# connectors.net
KiCad netlist of a schematic drawn in Altium Designer
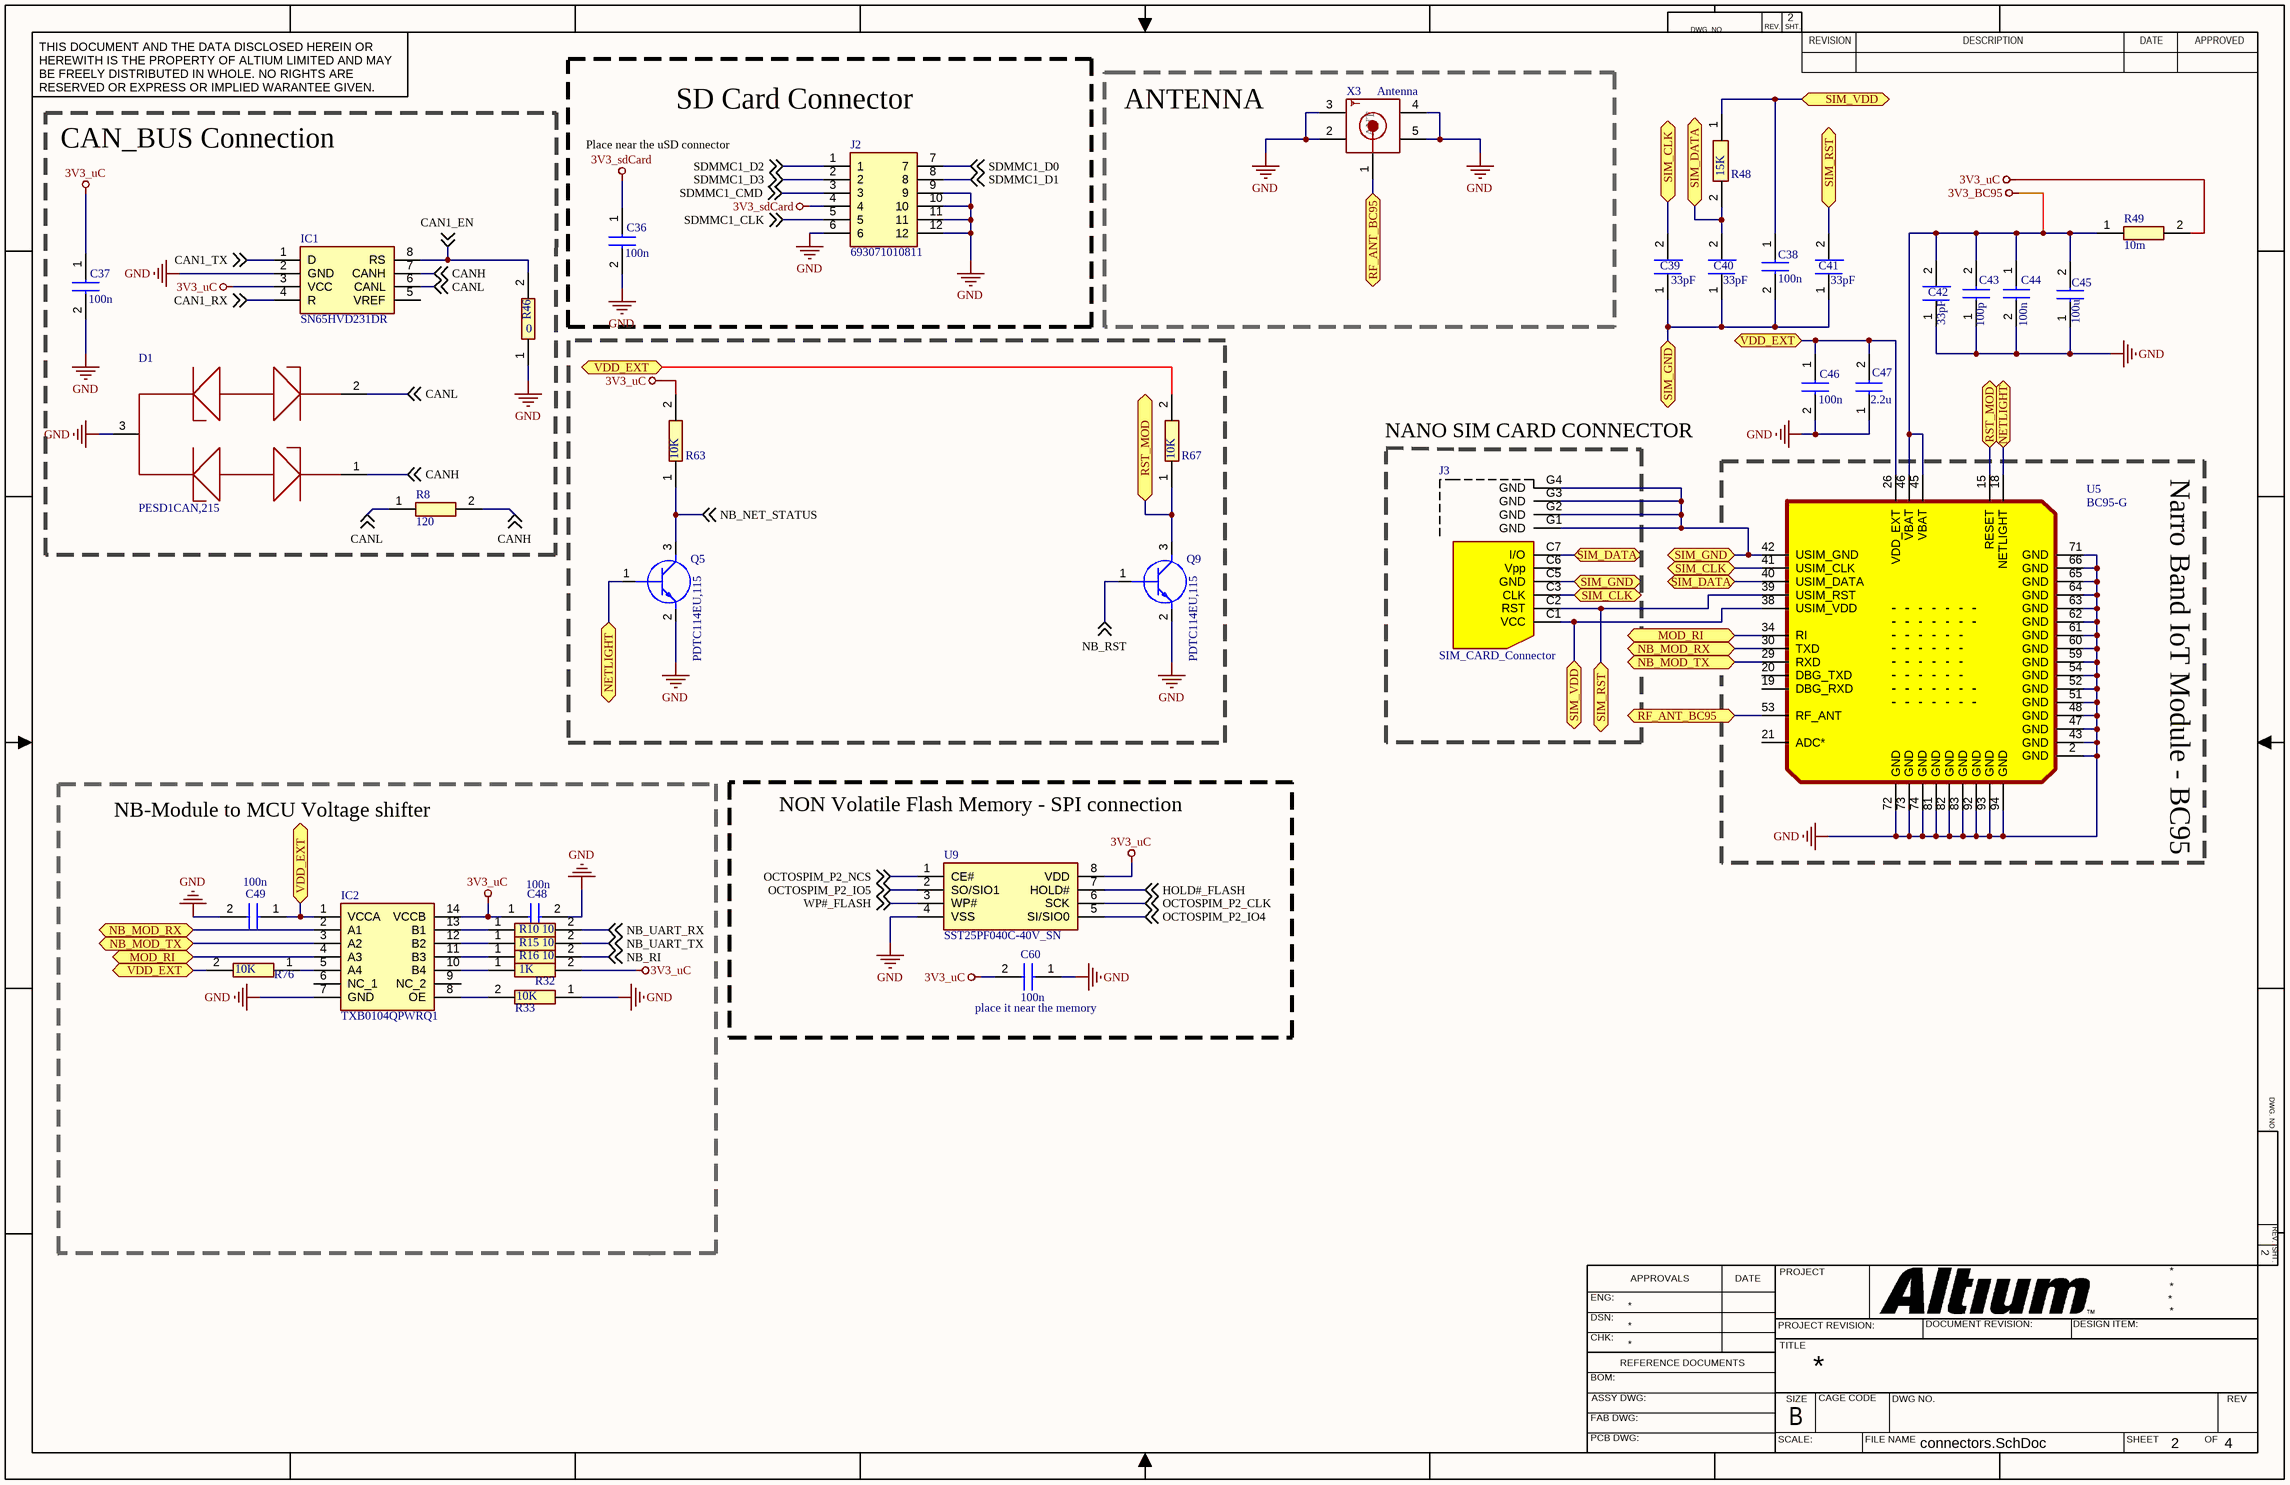
[diagram p0: connectors.SchDoc]

(export (version "E")
  (design (tool "Eeschema 10.0.6"))
  (components
    (comp (ref "C36")
      (value "100n")
      (footprint "SamacSys:CAPC1608X87N")
      (description "Capacitor")
      (fields (field (name "MANUFACTURER_PART_NUMBER") "885012206071"))
      (libsource (lib "*") (part "885012206071"))
    )
    (comp (ref "C37")
      (value "100n")
      (footprint "SamacSys:CAPC1608X87N")
      (description "Capacitor")
      (fields (field (name "MANUFACTURER_PART_NUMBER") "885012206071"))
      (libsource (lib "*") (part "885012206071"))
    )
    (comp (ref "C38")
      (value "100n")
      (footprint "SamacSys:CAPC1608X87N")
      (description "Capacitor")
      (fields (field (name "MANUFACTURER_PART_NUMBER") "885012206071"))
      (libsource (lib "*") (part "885012206071"))
    )
    (comp (ref "C39")
      (value "33pF")
      (footprint "CAPC1608X87N")
      (description "Cap Ceramic 33pF 25V C0G 10% SMD 0603 125°C Paper T/R")
      (fields
        (field (name "MANUFACTURER") "Vishay Vitramon")
        (field (name "MANUFACTURER PART NUMBER") "VJ0603A330KXXCW1BC")
      )
      (libsource (lib "shm_schem_lib") (part "VJ0603A330KXXCW1BC"))
    )
    (comp (ref "C40")
      (value "33pF")
      (footprint "CAPC1608X87N")
      (description "Cap Ceramic 33pF 25V C0G 10% SMD 0603 125°C Paper T/R")
      (fields
        (field (name "MANUFACTURER") "Vishay Vitramon")
        (field (name "MANUFACTURER PART NUMBER") "VJ0603A330KXXCW1BC")
      )
      (libsource (lib "shm_schem_lib") (part "VJ0603A330KXXCW1BC"))
    )
    (comp (ref "C41")
      (value "33pF")
      (footprint "CAPC1608X87N")
      (description "Cap Ceramic 33pF 25V C0G 10% SMD 0603 125°C Paper T/R")
      (fields
        (field (name "MANUFACTURER") "Vishay Vitramon")
        (field (name "MANUFACTURER PART NUMBER") "VJ0603A330KXXCW1BC")
      )
      (libsource (lib "shm_schem_lib") (part "VJ0603A330KXXCW1BC"))
    )
    (comp (ref "C42")
      (value "33pF")
      (footprint "CAPC1608X87N")
      (description "Cap Ceramic 33pF 25V C0G 10% SMD 0603 125°C Paper T/R")
      (fields
        (field (name "MANUFACTURER") "Vishay Vitramon")
        (field (name "MANUFACTURER PART NUMBER") "VJ0603A330KXXCW1BC")
      )
      (libsource (lib "shm_schem_lib") (part "VJ0603A330KXXCW1BC"))
    )
    (comp (ref "C43")
      (value "100p")
      (footprint "SamacSys:CAPC1608X87N")
      (description "Capacitor")
      (fields (field (name "MANUFACTURER_PART_NUMBER") "885012206003"))
      (libsource (lib "*") (part "885012206003"))
    )
    (comp (ref "C44")
      (value "100n")
      (footprint "SamacSys:CAPC1608X87N")
      (description "Capacitor")
      (fields (field (name "MANUFACTURER_PART_NUMBER") "885012206071"))
      (libsource (lib "*") (part "885012206071"))
    )
    (comp (ref "C45")
      (value "100u")
      (footprint "SamacSys:CAPC3216X180N")
      (description "Capacitor")
      (fields
        (field (name "MOUSER2 PART NUMBER") "81-GRM31CR60J107ME9L")
        (field (name "MANUFACTURER_PART_NUMBER") "GRM31CR60J107ME39L")
      )
      (libsource (lib "*") (part "GRM31CR60J107ME39L"))
    )
    (comp (ref "C46")
      (value "100n")
      (footprint "SamacSys:CAPC1608X87N")
      (description "Capacitor")
      (fields (field (name "MANUFACTURER_PART_NUMBER") "885012206071"))
      (libsource (lib "*") (part "885012206071"))
    )
    (comp (ref "C47")
      (value "2.2u")
      (footprint "SamacSys:CAPC1608X50N")
      (description "Capacitor")
      (fields (field (name "MANUFACTURER_PART_NUMBER") "EMK107BJ225KA-T"))
      (libsource (lib "*") (part "EMK107BJ225KA-T"))
    )
    (comp (ref "C48")
      (value "100n")
      (footprint "SamacSys:CAPC1608X87N")
      (description "Capacitor")
      (fields (field (name "MANUFACTURER_PART_NUMBER") "885012206071"))
      (libsource (lib "*") (part "885012206071"))
    )
    (comp (ref "C49")
      (value "100n")
      (footprint "SamacSys:CAPC1608X87N")
      (description "Capacitor")
      (fields (field (name "MANUFACTURER_PART_NUMBER") "885012206071"))
      (libsource (lib "*") (part "885012206071"))
    )
    (comp (ref "C60")
      (value "100n")
      (footprint "SamacSys:CAPC1608X87N")
      (description "Capacitor")
      (fields (field (name "MANUFACTURER_PART_NUMBER") "885012206071"))
      (libsource (lib "*") (part "885012206071"))
    )
    (comp (ref "D1")
      (value "PESD1CAN,215")
      (footprint "SOT95P230X110-3N")
      (description "ESD Suppressor Diode TVS Bi-Dir 24V Automotive 3-Pin SOT-23 T/R / TVS DIODE 24VWM 70VC SOT23")
      (fields (field (name "MANUFACTURER") "Nexperia"))
      (libsource (lib "shm_schem_lib") (part "PESD1CAN,215"))
    )
    (comp (ref "IC1")
      (value "SN65HVD231DR")
      (footprint "SamacSys:SOIC127P600X175-8N")
      (description "Integrated Circuit")
      (libsource (lib "*") (part "SN65HVD231DR"))
    )
    (comp (ref "IC2")
      (value "TXB0104QPWRQ1")
      (footprint "SOP65P640X120-14N")
      (description "Integrated Circuit")
      (fields (field (name "MOUSER2 PART NUMBER") "595-TXB0104QPWRQ1"))
      (libsource (lib "*") (part "TXB0104QPWRQ1"))
    )
    (comp (ref "J2")
      (value "693071010811")
      (footprint "SamacSys:693071010811")
      (description "Connector")
      (libsource (lib "*") (part "693071010811"))
    )
    (comp (ref "J3")
      (value "SIM_CARD_Connector")
      (footprint "SIM8060601400A")
      (description "Sim Nano Hinged, 6P, 1.40MM Prof")
      (fields
        (field (name "MANUFACTURER") "GCT")
        (field (name "MANUFACTURER PART NUMBER") "SIM8060-6-0-14-00-A")
      )
      (libsource (lib "shm_schem_lib") (part "SIM8060-6-0-14-00-A"))
    )
    (comp (ref "Q5")
      (value "PDTC114EU,115")
      (footprint "SamacSys:SOT65P210X110-3N")
      (description "Transistor BJT NPN")
      (fields (field (name "MOUSER2 PART NUMBER") "771-PDTC114EU115"))
      (libsource (lib "*") (part "PDTC114EU,115"))
    )
    (comp (ref "Q9")
      (value "PDTC114EU,115")
      (footprint "SamacSys:SOT65P210X110-3N")
      (description "Transistor BJT NPN")
      (fields (field (name "MOUSER2 PART NUMBER") "771-PDTC114EU115"))
      (libsource (lib "*") (part "PDTC114EU,115"))
    )
    (comp (ref "R8")
      (value "120")
      (footprint "ERA2V_(0402)")
      (description "Resistor")
      (fields (field (name "MANUFACTURER_PART_NUMBER") "ERA-2VEB1200X"))
      (libsource (lib "*") (part "ERA-2VEB1200X"))
    )
    (comp (ref "R10")
      (value "10")
      (footprint "SamacSys:RESC1005X40N")
      (description "Resistor")
      (fields (field (name "MANUFACTURER_PART_NUMBER") "CR0402-FX-10R0GLF"))
      (libsource (lib "*") (part "CR0402-FX-10R0GLF"))
    )
    (comp (ref "R15")
      (value "10")
      (footprint "SamacSys:RESC1005X40N")
      (description "Resistor")
      (fields (field (name "MANUFACTURER_PART_NUMBER") "CR0402-FX-10R0GLF"))
      (libsource (lib "*") (part "CR0402-FX-10R0GLF"))
    )
    (comp (ref "R16")
      (value "10")
      (footprint "SamacSys:RESC1005X40N")
      (description "Resistor")
      (fields (field (name "MANUFACTURER_PART_NUMBER") "CR0402-FX-10R0GLF"))
      (libsource (lib "*") (part "CR0402-FX-10R0GLF"))
    )
    (comp (ref "R32")
      (value "1K")
      (footprint "RESC1608X55N")
      (description "Resistor")
      (fields
        (field (name "MOUSER2 PART NUMBER") "71-CRCW06031K00FKEAC")
        (field (name "MANUFACTURER_PART_NUMBER") "CRCW06031K00FKEAC")
      )
      (libsource (lib "*") (part "CRCW06031K00FKEAC"))
    )
    (comp (ref "R33")
      (value "10K")
      (footprint "ERJ3EK_(0603)")
      (description "Resistor")
      (fields
        (field (name "MOUSER2 PART NUMBER") "667-ERJ-3EKF1002V")
        (field (name "MANUFACTURER_PART_NUMBER") "ERJ-3EKF1002V")
      )
      (libsource (lib "*") (part "ERJ-3EKF1002V"))
    )
    (comp (ref "R46")
      (value "0")
      (footprint "SamacSys:RESC1608X55N")
      (description "Resistor")
      (fields (field (name "MANUFACTURER_PART_NUMBER") "RC0603FR-070RL"))
      (libsource (lib "*") (part "RC0603FR-070RL"))
    )
    (comp (ref "R48")
      (value "15K")
      (footprint "RESC1508X50N")
      (description "Res Thick Film 0603 15K Ohm 1% 0.25W(1/4W) ±100ppm/°C Pad SMD Automotive Medical T/R")
      (fields
        (field (name "MANUFACTURER") "Vishay Dale")
        (field (name "MANUFACTURER PART NUMBER") "RCS060315K0FKEA")
      )
      (libsource (lib "shm_schem_lib") (part "RCS060315K0FKEA"))
    )
    (comp (ref "R49")
      (value "10m")
      (footprint "ERJ6_B_BW_R_LW_CW_D")
      (description "Resistor")
      (fields
        (field (name "MOUSER2 PART NUMBER") "667-ERJ-6CWDR010V")
        (field (name "MANUFACTURER_PART_NUMBER") "ERJ-6CWDR010V")
      )
      (libsource (lib "*") (part "ERJ-6CWDR010V"))
    )
    (comp (ref "R63")
      (value "10K")
      (footprint "SamacSys:ERJ3EK_(0603)")
      (description "Resistor")
      (fields
        (field (name "MOUSER2 PART NUMBER") "667-ERJ-3EKF1002V")
        (field (name "MANUFACTURER_PART_NUMBER") "ERJ-3EKF1002V")
      )
      (libsource (lib "") (part "ERJ-3EKF1002V_1"))
    )
    (comp (ref "R67")
      (value "10K")
      (footprint "SamacSys:ERJ3EK_(0603)")
      (description "Resistor")
      (fields
        (field (name "MOUSER2 PART NUMBER") "667-ERJ-3EKF1002V")
        (field (name "MANUFACTURER_PART_NUMBER") "ERJ-3EKF1002V")
      )
      (libsource (lib "") (part "ERJ-3EKF1002V_1"))
    )
    (comp (ref "R76")
      (value "10K")
      (footprint "SamacSys:ERJ3EK_(0603)")
      (description "Resistor")
      (fields
        (field (name "MOUSER2 PART NUMBER") "667-ERJ-3EKF1002V")
        (field (name "MANUFACTURER_PART_NUMBER") "ERJ-3EKF1002V")
      )
      (libsource (lib "*") (part "ERJ-3EKF1002V"))
    )
    (comp (ref "U5")
      (value "BC95-G")
      (footprint "XCVR_BC95GJB02STD")
      (description "NB IoT Click BC95 LTE CAT NB1 Module Add-On Board")
      (fields
        (field (name "MANUFACTURER") "mikroElektronika")
        (field (name "MANUFACTURER PART NUMBER") "MIKROE-3294")
      )
      (libsource (lib "shm_schem_lib") (part "MIKROE-3294"))
    )
    (comp (ref "U9")
      (value "SST25PF040C-40V_SN")
      (footprint "SamacSys:SOIC127P600X175-8N")
      (description "Integrated Circuit")
      (fields (field (name "MANUFACTURER_PART_NUMBER") "SST25PF040C-40V/SN"))
      (libsource (lib "*") (part "SST25PF040C-40V_SN"))
    )
    (comp (ref "X3")
      (value "Antenna")
      (footprint "PCBSMAFRAHT")
      (description "CONNSMAJACKR/A50OHMPCB")
      (fields
        (field (name "MANUFACTURER") "Taoglas")
        (field (name "MANUFACTURER PART NUMBER") "PCB.SMAFRA.HT")
      )
      (libsource (lib "shm_schem_lib") (part "PCB.SMAFRA.HT"))
    )
  )
  (nets
    (net (code "1") (name "/MOD_RI") (class "Default")
      (node (ref "IC2") (pin "4") (pinfunction "A3_4") (pintype "passive"))
      (node (ref "U5") (pin "34") (pinfunction "RI_34") (pintype "passive"))
    )
    (net (code "2") (name "/NB_MOD_RX") (class "Default")
      (node (ref "IC2") (pin "2") (pinfunction "A1_2") (pintype "passive"))
      (node (ref "U5") (pin "30") (pinfunction "TXD_30") (pintype "passive"))
    )
    (net (code "3") (name "/NB_MOD_TX") (class "Default")
      (node (ref "IC2") (pin "3") (pinfunction "A2_3") (pintype "passive"))
      (node (ref "U5") (pin "29") (pinfunction "RXD_29") (pintype "passive"))
    )
    (net (code "4") (name "/NETLIGHT") (class "Default")
      (node (ref "Q5") (pin "1") (pinfunction "B_1") (pintype "passive"))
      (node (ref "U5") (pin "18") (pinfunction "NETLIGHT_18") (pintype "passive"))
    )
    (net (code "5") (name "/RF_ANT_BC95") (class "Default")
      (node (ref "U5") (pin "53") (pinfunction "RF_ANT_53") (pintype "passive"))
      (node (ref "X3") (pin "1") (pinfunction "1_1") (pintype "passive"))
    )
    (net (code "6") (name "/RST_MOD") (class "Default")
      (node (ref "Q9") (pin "3") (pinfunction "C_3") (pintype "passive"))
      (node (ref "R67") (pin "1") (pinfunction "1_1") (pintype "passive"))
      (node (ref "U5") (pin "15") (pinfunction "RESET_15") (pintype "passive"))
    )
    (net (code "7") (name "/SIM_CLK") (class "Default")
      (node (ref "C39") (pin "2") (pinfunction "2_2") (pintype "passive"))
      (node (ref "J3") (pin "C3") (pinfunction "CLK_C3") (pintype "passive"))
      (node (ref "U5") (pin "41") (pinfunction "USIM_CLK_41") (pintype "passive"))
    )
    (net (code "8") (name "/SIM_DATA") (class "Default")
      (node (ref "C40") (pin "2") (pinfunction "2_2") (pintype "passive"))
      (node (ref "J3") (pin "C7") (pinfunction "I/O_C7") (pintype "passive"))
      (node (ref "R48") (pin "2") (pinfunction "2_2") (pintype "passive"))
      (node (ref "U5") (pin "40") (pinfunction "USIM_DATA_40") (pintype "passive"))
    )
    (net (code "9") (name "/SIM_GND") (class "Default")
      (node (ref "C38") (pin "2") (pinfunction "2_2") (pintype "passive"))
      (node (ref "C39") (pin "1") (pinfunction "1_1") (pintype "passive"))
      (node (ref "C40") (pin "1") (pinfunction "1_1") (pintype "passive"))
      (node (ref "C41") (pin "1") (pinfunction "1_1") (pintype "passive"))
      (node (ref "J3") (pin "C5") (pinfunction "GND_C5") (pintype "passive"))
      (node (ref "J3") (pin "G1") (pinfunction "GND_G1") (pintype "passive"))
      (node (ref "J3") (pin "G2") (pinfunction "GND_G2") (pintype "passive"))
      (node (ref "J3") (pin "G3") (pinfunction "GND_G3") (pintype "passive"))
      (node (ref "J3") (pin "G4") (pinfunction "GND_G4") (pintype "passive"))
      (node (ref "U5") (pin "42") (pinfunction "USIM_GND_42") (pintype "passive"))
    )
    (net (code "10") (name "/SIM_RST") (class "Default")
      (node (ref "C41") (pin "2") (pinfunction "2_2") (pintype "passive"))
      (node (ref "J3") (pin "C2") (pinfunction "RST_C2") (pintype "passive"))
      (node (ref "U5") (pin "39") (pinfunction "USIM_RST_39") (pintype "passive"))
    )
    (net (code "11") (name "/SIM_VDD") (class "Default")
      (node (ref "C38") (pin "1") (pinfunction "1_1") (pintype "passive"))
      (node (ref "J3") (pin "C1") (pinfunction "VCC_C1") (pintype "passive"))
      (node (ref "R48") (pin "1") (pinfunction "1_1") (pintype "passive"))
      (node (ref "U5") (pin "38") (pinfunction "USIM_VDD_38") (pintype "passive"))
    )
    (net (code "12") (name "/VDD_EXT") (class "Default")
      (node (ref "C46") (pin "1") (pinfunction "1_1") (pintype "passive"))
      (node (ref "C47") (pin "2") (pinfunction "2_2") (pintype "passive"))
      (node (ref "C49") (pin "1") (pinfunction "1_1") (pintype "passive"))
      (node (ref "IC2") (pin "1") (pinfunction "VCCA_1") (pintype "passive"))
      (node (ref "R67") (pin "2") (pinfunction "2_2") (pintype "passive"))
      (node (ref "R76") (pin "2") (pinfunction "2_2") (pintype "passive"))
      (node (ref "U5") (pin "26") (pinfunction "VDD_EXT_26") (pintype "passive"))
    )
    (net (code "13") (name "3V3_BC95") (class "Default")
      (node (ref "C42") (pin "2") (pinfunction "2_2") (pintype "passive"))
      (node (ref "C43") (pin "2") (pinfunction "2_2") (pintype "passive"))
      (node (ref "C44") (pin "1") (pinfunction "1_1") (pintype "passive"))
      (node (ref "C45") (pin "2") (pinfunction "2_2") (pintype "passive"))
      (node (ref "R49") (pin "1") (pinfunction "1_1") (pintype "passive"))
      (node (ref "U5") (pin "45") (pinfunction "VBAT_45") (pintype "passive"))
      (node (ref "U5") (pin "46") (pinfunction "VBAT_46") (pintype "passive"))
    )
    (net (code "14") (name "3V3_sdCard") (class "Default")
      (node (ref "C36") (pin "1") (pinfunction "1_1") (pintype "passive"))
      (node (ref "J2") (pin "4") (pinfunction "4_4") (pintype "passive"))
    )
    (net (code "15") (name "3V3_uC") (class "Default")
      (node (ref "C37") (pin "1") (pinfunction "1_1") (pintype "passive"))
      (node (ref "C48") (pin "1") (pinfunction "1_1") (pintype "passive"))
      (node (ref "C60") (pin "2") (pinfunction "2_2") (pintype "passive"))
      (node (ref "IC1") (pin "3") (pinfunction "VCC_3") (pintype "passive"))
      (node (ref "IC2") (pin "14") (pinfunction "VCCB_14") (pintype "passive"))
      (node (ref "R32") (pin "2") (pinfunction "2_2") (pintype "passive"))
      (node (ref "R49") (pin "2") (pinfunction "2_2") (pintype "passive"))
      (node (ref "R63") (pin "2") (pinfunction "2_2") (pintype "passive"))
      (node (ref "U9") (pin "8") (pinfunction "VDD_8") (pintype "passive"))
    )
    (net (code "16") (name "CAN1_EN") (class "Default")
      (node (ref "IC1") (pin "8") (pinfunction "RS_8") (pintype "passive"))
      (node (ref "R46") (pin "2") (pinfunction "2_2") (pintype "passive"))
    )
    (net (code "17") (name "CAN1_RX") (class "Default")
      (node (ref "IC1") (pin "4") (pinfunction "R_4") (pintype "passive"))
    )
    (net (code "18") (name "CAN1_TX") (class "Default")
      (node (ref "IC1") (pin "1") (pinfunction "D_1") (pintype "passive"))
    )
    (net (code "19") (name "CANH") (class "Default")
      (node (ref "D1") (pin "1") (pinfunction "1_1") (pintype "passive"))
      (node (ref "IC1") (pin "7") (pinfunction "CANH_7") (pintype "passive"))
      (node (ref "R8") (pin "2") (pinfunction "2_2") (pintype "passive"))
    )
    (net (code "20") (name "CANL") (class "Default")
      (node (ref "D1") (pin "2") (pinfunction "2_2") (pintype "passive"))
      (node (ref "IC1") (pin "6") (pinfunction "CANL_6") (pintype "passive"))
      (node (ref "R8") (pin "1") (pinfunction "1_1") (pintype "passive"))
    )
    (net (code "21") (name "GND") (class "Default")
      (node (ref "C36") (pin "2") (pinfunction "2_2") (pintype "passive"))
      (node (ref "C37") (pin "2") (pinfunction "2_2") (pintype "passive"))
      (node (ref "C42") (pin "1") (pinfunction "1_1") (pintype "passive"))
      (node (ref "C43") (pin "1") (pinfunction "1_1") (pintype "passive"))
      (node (ref "C44") (pin "2") (pinfunction "2_2") (pintype "passive"))
      (node (ref "C45") (pin "1") (pinfunction "1_1") (pintype "passive"))
      (node (ref "C46") (pin "2") (pinfunction "2_2") (pintype "passive"))
      (node (ref "C47") (pin "1") (pinfunction "1_1") (pintype "passive"))
      (node (ref "C48") (pin "2") (pinfunction "2_2") (pintype "passive"))
      (node (ref "C49") (pin "2") (pinfunction "2_2") (pintype "passive"))
      (node (ref "C60") (pin "1") (pinfunction "1_1") (pintype "passive"))
      (node (ref "D1") (pin "3") (pinfunction "3_3") (pintype "passive"))
      (node (ref "IC1") (pin "2") (pinfunction "GND_2") (pintype "passive"))
      (node (ref "IC2") (pin "7") (pinfunction "GND_7") (pintype "passive"))
      (node (ref "J2") (pin "10") (pinfunction "10_10") (pintype "passive"))
      (node (ref "J2") (pin "11") (pinfunction "11_11") (pintype "passive"))
      (node (ref "J2") (pin "12") (pinfunction "12_12") (pintype "passive"))
      (node (ref "J2") (pin "6") (pinfunction "6_6") (pintype "passive"))
      (node (ref "J2") (pin "9") (pinfunction "9_9") (pintype "passive"))
      (node (ref "Q5") (pin "2") (pinfunction "E_2") (pintype "passive"))
      (node (ref "Q9") (pin "2") (pinfunction "E_2") (pintype "passive"))
      (node (ref "R33") (pin "1") (pinfunction "1_1") (pintype "passive"))
      (node (ref "R46") (pin "1") (pinfunction "1_1") (pintype "passive"))
      (node (ref "U5") (pin "2") (pinfunction "GND_2") (pintype "passive"))
      (node (ref "U5") (pin "43") (pinfunction "GND_43") (pintype "passive"))
      (node (ref "U5") (pin "47") (pinfunction "GND_47") (pintype "passive"))
      (node (ref "U5") (pin "48") (pinfunction "GND_48") (pintype "passive"))
      (node (ref "U5") (pin "51") (pinfunction "GND_51") (pintype "passive"))
      (node (ref "U5") (pin "52") (pinfunction "GND_52") (pintype "passive"))
      (node (ref "U5") (pin "54") (pinfunction "GND_54") (pintype "passive"))
      (node (ref "U5") (pin "59") (pinfunction "GND_59") (pintype "passive"))
      (node (ref "U5") (pin "60") (pinfunction "GND_60") (pintype "passive"))
      (node (ref "U5") (pin "61") (pinfunction "GND_61") (pintype "passive"))
      (node (ref "U5") (pin "62") (pinfunction "GND_62") (pintype "passive"))
      (node (ref "U5") (pin "63") (pinfunction "GND_63") (pintype "passive"))
      (node (ref "U5") (pin "64") (pinfunction "GND_64") (pintype "passive"))
      (node (ref "U5") (pin "65") (pinfunction "GND_65") (pintype "passive"))
      (node (ref "U5") (pin "66") (pinfunction "GND_66") (pintype "passive"))
      (node (ref "U5") (pin "71") (pinfunction "GND_71") (pintype "passive"))
      (node (ref "U5") (pin "72") (pinfunction "GND_72") (pintype "passive"))
      (node (ref "U5") (pin "73") (pinfunction "GND_73") (pintype "passive"))
      (node (ref "U5") (pin "74") (pinfunction "GND_74") (pintype "passive"))
      (node (ref "U5") (pin "81") (pinfunction "GND_81") (pintype "passive"))
      (node (ref "U5") (pin "82") (pinfunction "GND_82") (pintype "passive"))
      (node (ref "U5") (pin "83") (pinfunction "GND_83") (pintype "passive"))
      (node (ref "U5") (pin "92") (pinfunction "GND_92") (pintype "passive"))
      (node (ref "U5") (pin "93") (pinfunction "GND_93") (pintype "passive"))
      (node (ref "U5") (pin "94") (pinfunction "GND_94") (pintype "passive"))
      (node (ref "U9") (pin "4") (pinfunction "VSS_4") (pintype "passive"))
      (node (ref "X3") (pin "2") (pinfunction "2_2") (pintype "passive"))
      (node (ref "X3") (pin "3") (pinfunction "3_3") (pintype "passive"))
      (node (ref "X3") (pin "4") (pinfunction "4_4") (pintype "passive"))
      (node (ref "X3") (pin "5") (pinfunction "5_5") (pintype "passive"))
    )
    (net (code "22") (name "HOLD#_FLASH") (class "Default")
      (node (ref "U9") (pin "7") (pinfunction "HOLD#_7") (pintype "passive"))
    )
    (net (code "23") (name "NB_NET_STATUS") (class "Default")
      (node (ref "Q5") (pin "3") (pinfunction "C_3") (pintype "passive"))
      (node (ref "R63") (pin "1") (pinfunction "1_1") (pintype "passive"))
    )
    (net (code "24") (name "NB_RI") (class "Default")
      (node (ref "R16") (pin "2") (pinfunction "2_2") (pintype "passive"))
    )
    (net (code "25") (name "NB_RST") (class "Default")
      (node (ref "Q9") (pin "1") (pinfunction "B_1") (pintype "passive"))
    )
    (net (code "26") (name "NB_UART_RX") (class "Default")
      (node (ref "R10") (pin "2") (pinfunction "2_2") (pintype "passive"))
    )
    (net (code "27") (name "NB_UART_TX") (class "Default")
      (node (ref "R15") (pin "2") (pinfunction "2_2") (pintype "passive"))
    )
    (net (code "28") (name "Net-(IC2-A4)") (class "Default")
      (node (ref "IC2") (pin "5") (pinfunction "A4_5") (pintype "passive"))
      (node (ref "R76") (pin "1") (pinfunction "1_1") (pintype "passive"))
    )
    (net (code "29") (name "Net-(IC2-B1)") (class "Default")
      (node (ref "IC2") (pin "13") (pinfunction "B1_13") (pintype "passive"))
      (node (ref "R10") (pin "1") (pinfunction "1_1") (pintype "passive"))
    )
    (net (code "30") (name "Net-(IC2-B2)") (class "Default")
      (node (ref "IC2") (pin "12") (pinfunction "B2_12") (pintype "passive"))
      (node (ref "R15") (pin "1") (pinfunction "1_1") (pintype "passive"))
    )
    (net (code "31") (name "Net-(IC2-B3)") (class "Default")
      (node (ref "IC2") (pin "11") (pinfunction "B3_11") (pintype "passive"))
      (node (ref "R16") (pin "1") (pinfunction "1_1") (pintype "passive"))
    )
    (net (code "32") (name "Net-(IC2-B4)") (class "Default")
      (node (ref "IC2") (pin "10") (pinfunction "B4_10") (pintype "passive"))
      (node (ref "R32") (pin "1") (pinfunction "1_1") (pintype "passive"))
    )
    (net (code "33") (name "Net-(IC2-OE)") (class "Default")
      (node (ref "IC2") (pin "8") (pinfunction "OE_8") (pintype "passive"))
      (node (ref "R33") (pin "2") (pinfunction "2_2") (pintype "passive"))
    )
    (net (code "34") (name "OCTOSPIM_P2_CLK") (class "Default")
      (node (ref "U9") (pin "6") (pinfunction "SCK_6") (pintype "passive"))
    )
    (net (code "35") (name "OCTOSPIM_P2_IO4") (class "Default")
      (node (ref "U9") (pin "5") (pinfunction "SI/SIO0_5") (pintype "passive"))
    )
    (net (code "36") (name "OCTOSPIM_P2_IO5") (class "Default")
      (node (ref "U9") (pin "2") (pinfunction "SO/SIO1_2") (pintype "passive"))
    )
    (net (code "37") (name "OCTOSPIM_P2_NCS") (class "Default")
      (node (ref "U9") (pin "1") (pinfunction "CE#_1") (pintype "passive"))
    )
    (net (code "38") (name "SDMMC1_CLK") (class "Default")
      (node (ref "J2") (pin "5") (pinfunction "5_5") (pintype "passive"))
    )
    (net (code "39") (name "SDMMC1_CMD") (class "Default")
      (node (ref "J2") (pin "3") (pinfunction "3_3") (pintype "passive"))
    )
    (net (code "40") (name "SDMMC1_D0") (class "Default")
      (node (ref "J2") (pin "7") (pinfunction "7_7") (pintype "passive"))
    )
    (net (code "41") (name "SDMMC1_D1") (class "Default")
      (node (ref "J2") (pin "8") (pinfunction "8_8") (pintype "passive"))
    )
    (net (code "42") (name "SDMMC1_D2") (class "Default")
      (node (ref "J2") (pin "1") (pinfunction "1_1") (pintype "passive"))
    )
    (net (code "43") (name "SDMMC1_D3") (class "Default")
      (node (ref "J2") (pin "2") (pinfunction "2_2") (pintype "passive"))
    )
    (net (code "44") (name "WP#_FLASH") (class "Default")
      (node (ref "U9") (pin "3") (pinfunction "WP#_3") (pintype "passive"))
    )
    (net (code "45") (name "unconnected-(IC1-VREF-Pad5)") (class "Default")
      (node (ref "IC1") (pin "5") (pinfunction "VREF_5") (pintype "passive"))
    )
    (net (code "46") (name "unconnected-(IC2-NC_1-Pad6)") (class "Default")
      (node (ref "IC2") (pin "6") (pinfunction "NC_1_6") (pintype "passive"))
    )
    (net (code "47") (name "unconnected-(IC2-NC_2-Pad9)") (class "Default")
      (node (ref "IC2") (pin "9") (pinfunction "NC_2_9") (pintype "passive"))
    )
    (net (code "48") (name "unconnected-(J3-Vpp-PadC6)") (class "Default")
      (node (ref "J3") (pin "C6") (pinfunction "Vpp_C6") (pintype "passive"))
    )
    (net (code "49") (name "unconnected-(U5-ADC*-Pad21)") (class "Default")
      (node (ref "U5") (pin "21") (pinfunction "ADC*_21") (pintype "passive"))
    )
    (net (code "50") (name "unconnected-(U5-DBG_RXD-Pad19)") (class "Default")
      (node (ref "U5") (pin "19") (pinfunction "DBG_RXD_19") (pintype "passive"))
    )
    (net (code "51") (name "unconnected-(U5-DBG_TXD-Pad20)") (class "Default")
      (node (ref "U5") (pin "20") (pinfunction "DBG_TXD_20") (pintype "passive"))
    )
    (net (code "52") (name "unconnected-(U5-RESERVED-Pad1)") (class "Default")
      (node (ref "U5") (pin "1") (pinfunction "RESERVED_1") (pintype "passive"))
    )
    (net (code "53") (name "unconnected-(U5-RESERVED-Pad3)") (class "Default")
      (node (ref "U5") (pin "3") (pinfunction "RESERVED_3") (pintype "passive"))
    )
    (net (code "54") (name "unconnected-(U5-RESERVED-Pad4)") (class "Default")
      (node (ref "U5") (pin "4") (pinfunction "RESERVED_4") (pintype "passive"))
    )
    (net (code "55") (name "unconnected-(U5-RESERVED-Pad5)") (class "Default")
      (node (ref "U5") (pin "5") (pinfunction "RESERVED_5") (pintype "passive"))
    )
    (net (code "56") (name "unconnected-(U5-RESERVED-Pad6)") (class "Default")
      (node (ref "U5") (pin "6") (pinfunction "RESERVED_6") (pintype "passive"))
    )
    (net (code "57") (name "unconnected-(U5-RESERVED-Pad7)") (class "Default")
      (node (ref "U5") (pin "7") (pinfunction "RESERVED_7") (pintype "passive"))
    )
    (net (code "58") (name "unconnected-(U5-RESERVED-Pad8)") (class "Default")
      (node (ref "U5") (pin "8") (pinfunction "RESERVED_8") (pintype "passive"))
    )
    (net (code "59") (name "unconnected-(U5-RESERVED-Pad9)") (class "Default")
      (node (ref "U5") (pin "9") (pinfunction "RESERVED_9") (pintype "passive"))
    )
    (net (code "60") (name "unconnected-(U5-RESERVED-Pad10)") (class "Default")
      (node (ref "U5") (pin "10") (pinfunction "RESERVED_10") (pintype "passive"))
    )
    (net (code "61") (name "unconnected-(U5-RESERVED-Pad11)") (class "Default")
      (node (ref "U5") (pin "11") (pinfunction "RESERVED_11") (pintype "passive"))
    )
    (net (code "62") (name "unconnected-(U5-RESERVED-Pad12)") (class "Default")
      (node (ref "U5") (pin "12") (pinfunction "RESERVED_12") (pintype "passive"))
    )
    (net (code "63") (name "unconnected-(U5-RESERVED-Pad13)") (class "Default")
      (node (ref "U5") (pin "13") (pinfunction "RESERVED_13") (pintype "passive"))
    )
    (net (code "64") (name "unconnected-(U5-RESERVED-Pad14)") (class "Default")
      (node (ref "U5") (pin "14") (pinfunction "RESERVED_14") (pintype "passive"))
    )
    (net (code "65") (name "unconnected-(U5-RESERVED-Pad16)") (class "Default")
      (node (ref "U5") (pin "16") (pinfunction "RESERVED_16") (pintype "passive"))
    )
    (net (code "66") (name "unconnected-(U5-RESERVED-Pad17)") (class "Default")
      (node (ref "U5") (pin "17") (pinfunction "RESERVED_17") (pintype "passive"))
    )
    (net (code "67") (name "unconnected-(U5-RESERVED-Pad22)") (class "Default")
      (node (ref "U5") (pin "22") (pinfunction "RESERVED_22") (pintype "passive"))
    )
    (net (code "68") (name "unconnected-(U5-RESERVED-Pad23)") (class "Default")
      (node (ref "U5") (pin "23") (pinfunction "RESERVED_23") (pintype "passive"))
    )
    (net (code "69") (name "unconnected-(U5-RESERVED-Pad24)") (class "Default")
      (node (ref "U5") (pin "24") (pinfunction "RESERVED_24") (pintype "passive"))
    )
    (net (code "70") (name "unconnected-(U5-RESERVED-Pad25)") (class "Default")
      (node (ref "U5") (pin "25") (pinfunction "RESERVED_25") (pintype "passive"))
    )
    (net (code "71") (name "unconnected-(U5-RESERVED-Pad27)") (class "Default")
      (node (ref "U5") (pin "27") (pinfunction "RESERVED_27") (pintype "passive"))
    )
    (net (code "72") (name "unconnected-(U5-RESERVED-Pad28)") (class "Default")
      (node (ref "U5") (pin "28") (pinfunction "RESERVED_28") (pintype "passive"))
    )
    (net (code "73") (name "unconnected-(U5-RESERVED-Pad31)") (class "Default")
      (node (ref "U5") (pin "31") (pinfunction "RESERVED_31") (pintype "passive"))
    )
    (net (code "74") (name "unconnected-(U5-RESERVED-Pad32)") (class "Default")
      (node (ref "U5") (pin "32") (pinfunction "RESERVED_32") (pintype "passive"))
    )
    (net (code "75") (name "unconnected-(U5-RESERVED-Pad33)") (class "Default")
      (node (ref "U5") (pin "33") (pinfunction "RESERVED_33") (pintype "passive"))
    )
    (net (code "76") (name "unconnected-(U5-RESERVED-Pad35)") (class "Default")
      (node (ref "U5") (pin "35") (pinfunction "RESERVED_35") (pintype "passive"))
    )
    (net (code "77") (name "unconnected-(U5-RESERVED-Pad36)") (class "Default")
      (node (ref "U5") (pin "36") (pinfunction "RESERVED_36") (pintype "passive"))
    )
    (net (code "78") (name "unconnected-(U5-RESERVED-Pad37)") (class "Default")
      (node (ref "U5") (pin "37") (pinfunction "RESERVED_37") (pintype "passive"))
    )
    (net (code "79") (name "unconnected-(U5-RESERVED-Pad44)") (class "Default")
      (node (ref "U5") (pin "44") (pinfunction "RESERVED_44") (pintype "passive"))
    )
    (net (code "80") (name "unconnected-(U5-RESERVED-Pad49)") (class "Default")
      (node (ref "U5") (pin "49") (pinfunction "RESERVED_49") (pintype "passive"))
    )
    (net (code "81") (name "unconnected-(U5-RESERVED-Pad50)") (class "Default")
      (node (ref "U5") (pin "50") (pinfunction "RESERVED_50") (pintype "passive"))
    )
    (net (code "82") (name "unconnected-(U5-RESERVED-Pad55)") (class "Default")
      (node (ref "U5") (pin "55") (pinfunction "RESERVED_55") (pintype "passive"))
    )
    (net (code "83") (name "unconnected-(U5-RESERVED-Pad56)") (class "Default")
      (node (ref "U5") (pin "56") (pinfunction "RESERVED_56") (pintype "passive"))
    )
    (net (code "84") (name "unconnected-(U5-RESERVED-Pad57)") (class "Default")
      (node (ref "U5") (pin "57") (pinfunction "RESERVED_57") (pintype "passive"))
    )
    (net (code "85") (name "unconnected-(U5-RESERVED-Pad58)") (class "Default")
      (node (ref "U5") (pin "58") (pinfunction "RESERVED_58") (pintype "passive"))
    )
    (net (code "86") (name "unconnected-(U5-RESERVED-Pad67)") (class "Default")
      (node (ref "U5") (pin "67") (pinfunction "RESERVED_67") (pintype "passive"))
    )
    (net (code "87") (name "unconnected-(U5-RESERVED-Pad68)") (class "Default")
      (node (ref "U5") (pin "68") (pinfunction "RESERVED_68") (pintype "passive"))
    )
    (net (code "88") (name "unconnected-(U5-RESERVED-Pad69)") (class "Default")
      (node (ref "U5") (pin "69") (pinfunction "RESERVED_69") (pintype "passive"))
    )
    (net (code "89") (name "unconnected-(U5-RESERVED-Pad70)") (class "Default")
      (node (ref "U5") (pin "70") (pinfunction "RESERVED_70") (pintype "passive"))
    )
    (net (code "90") (name "unconnected-(U5-RESERVED-Pad75)") (class "Default")
      (node (ref "U5") (pin "75") (pinfunction "RESERVED_75") (pintype "passive"))
    )
    (net (code "91") (name "unconnected-(U5-RESERVED-Pad76)") (class "Default")
      (node (ref "U5") (pin "76") (pinfunction "RESERVED_76") (pintype "passive"))
    )
    (net (code "92") (name "unconnected-(U5-RESERVED-Pad77)") (class "Default")
      (node (ref "U5") (pin "77") (pinfunction "RESERVED_77") (pintype "passive"))
    )
    (net (code "93") (name "unconnected-(U5-RESERVED-Pad78)") (class "Default")
      (node (ref "U5") (pin "78") (pinfunction "RESERVED_78") (pintype "passive"))
    )
    (net (code "94") (name "unconnected-(U5-RESERVED-Pad79)") (class "Default")
      (node (ref "U5") (pin "79") (pinfunction "RESERVED_79") (pintype "passive"))
    )
    (net (code "95") (name "unconnected-(U5-RESERVED-Pad80)") (class "Default")
      (node (ref "U5") (pin "80") (pinfunction "RESERVED_80") (pintype "passive"))
    )
    (net (code "96") (name "unconnected-(U5-RESERVED-Pad84)") (class "Default")
      (node (ref "U5") (pin "84") (pinfunction "RESERVED_84") (pintype "passive"))
    )
    (net (code "97") (name "unconnected-(U5-RESERVED-Pad85)") (class "Default")
      (node (ref "U5") (pin "85") (pinfunction "RESERVED_85") (pintype "passive"))
    )
    (net (code "98") (name "unconnected-(U5-RESERVED-Pad86)") (class "Default")
      (node (ref "U5") (pin "86") (pinfunction "RESERVED_86") (pintype "passive"))
    )
    (net (code "99") (name "unconnected-(U5-RESERVED-Pad87)") (class "Default")
      (node (ref "U5") (pin "87") (pinfunction "RESERVED_87") (pintype "passive"))
    )
    (net (code "100") (name "unconnected-(U5-RESERVED-Pad88)") (class "Default")
      (node (ref "U5") (pin "88") (pinfunction "RESERVED_88") (pintype "passive"))
    )
    (net (code "101") (name "unconnected-(U5-RESERVED-Pad89)") (class "Default")
      (node (ref "U5") (pin "89") (pinfunction "RESERVED_89") (pintype "passive"))
    )
    (net (code "102") (name "unconnected-(U5-RESERVED-Pad90)") (class "Default")
      (node (ref "U5") (pin "90") (pinfunction "RESERVED_90") (pintype "passive"))
    )
    (net (code "103") (name "unconnected-(U5-RESERVED-Pad91)") (class "Default")
      (node (ref "U5") (pin "91") (pinfunction "RESERVED_91") (pintype "passive"))
    )
  )
)
